# Esquematico.net
KiCad netlist of a schematic drawn in Altium Designer
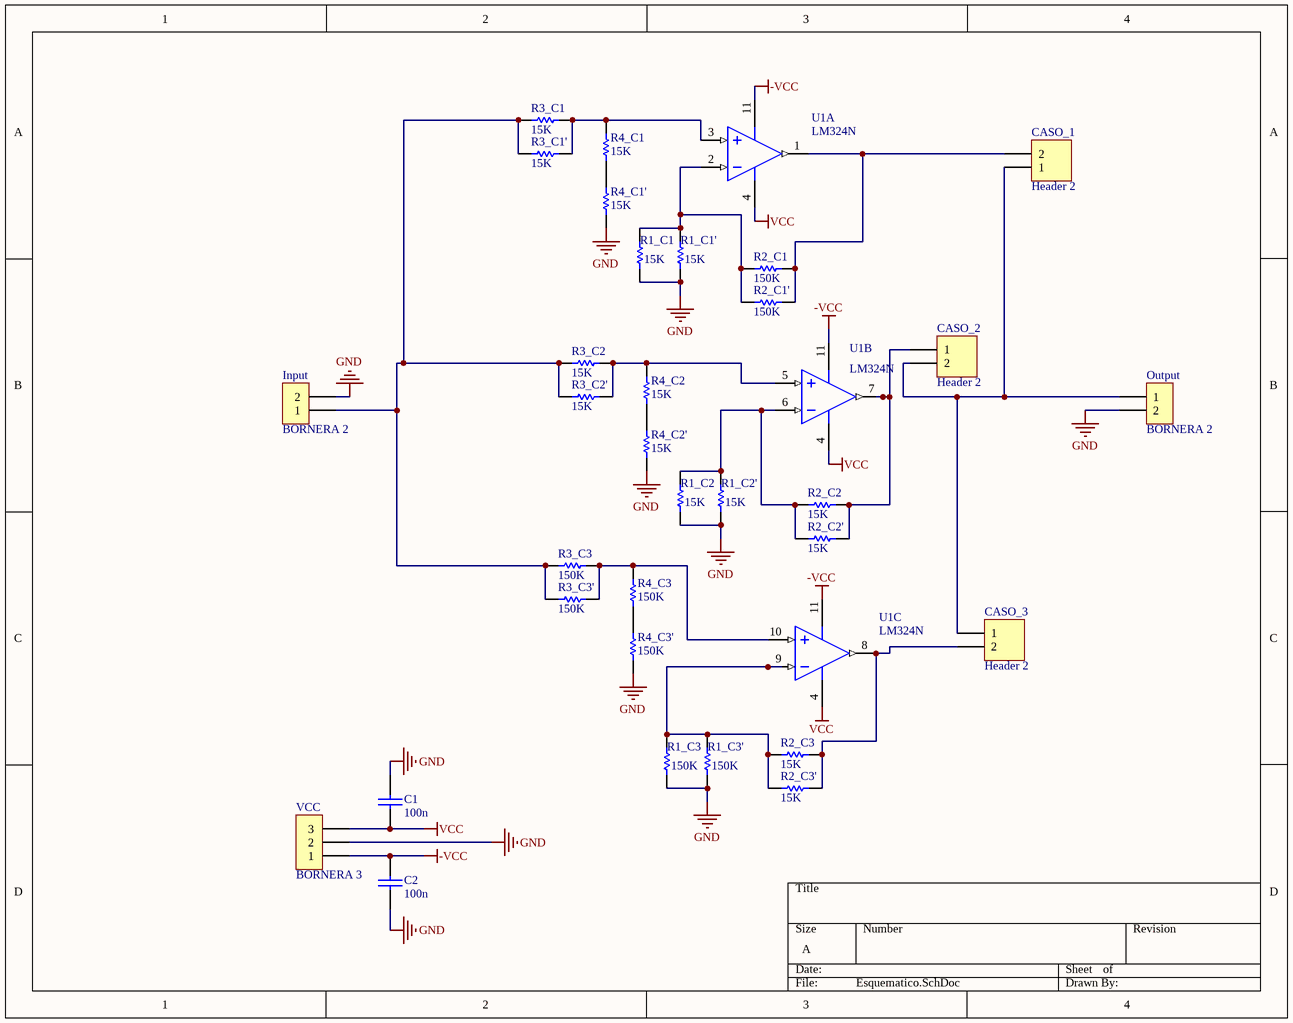
[diagram p0: Esquematico.SchDoc]

(export (version "E")
  (design (tool "Eeschema 10.0.6"))
  (components
    (comp (ref "C1") (value "100n") (footprint "CAP100") (libsource (lib "LIBEBAL") (part "CAP")))
    (comp (ref "C2") (value "100n") (footprint "CAP100") (libsource (lib "LIBEBAL") (part "CAP")))
    (comp (ref "CASO_1")
      (value "Header 2")
      (footprint "HDR1X2")
      (description "Header, 2-Pin")
      (fields (field (name "PUBLISHER") "Altium Limited"))
      (libsource (lib "") (part "Header 2_1"))
    )
    (comp (ref "CASO_2")
      (value "Header 2")
      (footprint "HDR1X2")
      (description "Header, 2-Pin")
      (fields (field (name "PUBLISHER") "Altium Limited"))
      (libsource (lib "Miscellaneous Connectors") (part "Header 2"))
    )
    (comp (ref "CASO_3")
      (value "Header 2")
      (footprint "HDR1X2")
      (description "Header, 2-Pin")
      (fields (field (name "PUBLISHER") "Altium Limited"))
      (libsource (lib "Miscellaneous Connectors") (part "Header 2"))
    )
    (comp (ref "Input") (value "BORNERA 2") (footprint "BORNERA2") (libsource (lib "") (part "BORNERA 2_1")))
    (comp (ref "Output")
      (value "BORNERA 2")
      (footprint "BORNERA2")
      (libsource (lib "LIB PIO IX") (part "BORNERA 2"))
    )
    (comp (ref "R1_C1") (value "15K") (footprint "RES400") (libsource (lib "LIBEBAL") (part "RES")))
    (comp (ref "R1_C1'") (value "15K") (footprint "RES400") (libsource (lib "LIBEBAL") (part "RES")))
    (comp (ref "R1_C2") (value "15K") (footprint "RES400") (libsource (lib "LIBEBAL") (part "RES")))
    (comp (ref "R1_C2'") (value "15K") (footprint "RES400") (libsource (lib "LIBEBAL") (part "RES")))
    (comp (ref "R1_C3") (value "150K") (footprint "RES400") (libsource (lib "LIBEBAL") (part "RES")))
    (comp (ref "R1_C3'") (value "150K") (footprint "RES400") (libsource (lib "LIBEBAL") (part "RES")))
    (comp (ref "R2_C1") (value "150K") (footprint "RES400") (libsource (lib "LIBEBAL") (part "RES")))
    (comp (ref "R2_C1'") (value "150K") (footprint "RES400") (libsource (lib "LIBEBAL") (part "RES")))
    (comp (ref "R2_C2") (value "15K") (footprint "RES400") (libsource (lib "LIBEBAL") (part "RES")))
    (comp (ref "R2_C2'") (value "15K") (footprint "RES400") (libsource (lib "LIBEBAL") (part "RES")))
    (comp (ref "R2_C3") (value "15K") (footprint "RES400") (libsource (lib "LIBEBAL") (part "RES")))
    (comp (ref "R2_C3'") (value "15K") (footprint "RES400") (libsource (lib "LIBEBAL") (part "RES")))
    (comp (ref "R3_C1") (value "15K") (footprint "RES400") (libsource (lib "LIBEBAL") (part "RES")))
    (comp (ref "R3_C1'") (value "15K") (footprint "RES400") (libsource (lib "LIBEBAL") (part "RES")))
    (comp (ref "R3_C2") (value "15K") (footprint "RES400") (libsource (lib "LIBEBAL") (part "RES")))
    (comp (ref "R3_C2'") (value "15K") (footprint "RES400") (libsource (lib "LIBEBAL") (part "RES")))
    (comp (ref "R3_C3") (value "150K") (footprint "RES400") (libsource (lib "LIBEBAL") (part "RES")))
    (comp (ref "R3_C3'") (value "150K") (footprint "RES400") (libsource (lib "LIBEBAL") (part "RES")))
    (comp (ref "R4_C1") (value "15K") (footprint "RES400") (libsource (lib "LIBEBAL") (part "RES")))
    (comp (ref "R4_C1'") (value "15K") (footprint "RES400") (libsource (lib "LIBEBAL") (part "RES")))
    (comp (ref "R4_C2") (value "15K") (footprint "RES400") (libsource (lib "LIBEBAL") (part "RES")))
    (comp (ref "R4_C2'") (value "15K") (footprint "RES400") (libsource (lib "LIBEBAL") (part "RES")))
    (comp (ref "R4_C3") (value "150K") (footprint "RES400") (libsource (lib "LIBEBAL") (part "RES")))
    (comp (ref "R4_C3'") (value "150K") (footprint "RES400") (libsource (lib "LIBEBAL") (part "RES")))
    (comp (ref "U1")
      (value "LM324N")
      (footprint "N14A")
      (description "Low Power Quad Operational Amplifier, 14-pin MDIP")
      (fields
        (field (name "MANUFACTURER") "National Semiconductor")
        (field (name "PUBLISHER") "Altium Limited")
      )
      (libsource (lib "NSC Amplifier") (part "LM324N"))
    )
    (comp (ref "VCC")
      (value "BORNERA 3")
      (footprint "BORNERA3")
      (libsource (lib "LIB PIO IX") (part "BORNERA 3"))
    )
  )
  (nets
    (net (code "1") (name "-VCC") (class "Default")
      (node (ref "C2") (pin "1") (pinfunction "1_1") (pintype "passive"))
      (node (ref "U1") (pin "11") (pinfunction "GND_11") (pintype "power_in"))
      (node (ref "VCC") (pin "1") (pinfunction "1_1") (pintype "passive"))
    )
    (net (code "2") (name "GND") (class "Default")
      (node (ref "C1") (pin "1") (pinfunction "1_1") (pintype "passive"))
      (node (ref "C2") (pin "2") (pinfunction "2_2") (pintype "passive"))
      (node (ref "Input") (pin "2") (pinfunction "2_2") (pintype "passive"))
      (node (ref "Output") (pin "2") (pinfunction "2_2") (pintype "passive"))
      (node (ref "R1_C1") (pin "1") (pinfunction "1_1") (pintype "passive"))
      (node (ref "R1_C1'") (pin "1") (pinfunction "1_1") (pintype "passive"))
      (node (ref "R1_C2") (pin "1") (pinfunction "1_1") (pintype "passive"))
      (node (ref "R1_C2'") (pin "1") (pinfunction "1_1") (pintype "passive"))
      (node (ref "R1_C3") (pin "1") (pinfunction "1_1") (pintype "passive"))
      (node (ref "R1_C3'") (pin "1") (pinfunction "1_1") (pintype "passive"))
      (node (ref "R4_C1'") (pin "1") (pinfunction "1_1") (pintype "passive"))
      (node (ref "R4_C2'") (pin "1") (pinfunction "1_1") (pintype "passive"))
      (node (ref "R4_C3'") (pin "1") (pinfunction "1_1") (pintype "passive"))
      (node (ref "VCC") (pin "2") (pinfunction "2_2") (pintype "passive"))
    )
    (net (code "3") (name "Net-(CASO_1-Pad1)") (class "Default")
      (node (ref "CASO_1") (pin "1") (pinfunction "1_1") (pintype "passive"))
      (node (ref "CASO_2") (pin "2") (pinfunction "2_2") (pintype "passive"))
      (node (ref "CASO_3") (pin "1") (pinfunction "1_1") (pintype "passive"))
      (node (ref "Output") (pin "1") (pinfunction "1_1") (pintype "passive"))
    )
    (net (code "4") (name "Net-(Input-Pad1)") (class "Default")
      (node (ref "Input") (pin "1") (pinfunction "1_1") (pintype "passive"))
      (node (ref "R3_C1") (pin "1") (pinfunction "1_1") (pintype "passive"))
      (node (ref "R3_C1'") (pin "1") (pinfunction "1_1") (pintype "passive"))
      (node (ref "R3_C2") (pin "1") (pinfunction "1_1") (pintype "passive"))
      (node (ref "R3_C2'") (pin "1") (pinfunction "1_1") (pintype "passive"))
      (node (ref "R3_C3") (pin "1") (pinfunction "1_1") (pintype "passive"))
      (node (ref "R3_C3'") (pin "1") (pinfunction "1_1") (pintype "passive"))
    )
    (net (code "5") (name "Net-(R4_C1'-Pad2)") (class "Default")
      (node (ref "R4_C1") (pin "1") (pinfunction "1_1") (pintype "passive"))
      (node (ref "R4_C1'") (pin "2") (pinfunction "2_2") (pintype "passive"))
    )
    (net (code "6") (name "Net-(R4_C2'-Pad2)") (class "Default")
      (node (ref "R4_C2") (pin "1") (pinfunction "1_1") (pintype "passive"))
      (node (ref "R4_C2'") (pin "2") (pinfunction "2_2") (pintype "passive"))
    )
    (net (code "7") (name "Net-(R4_C3'-Pad2)") (class "Default")
      (node (ref "R4_C3") (pin "1") (pinfunction "1_1") (pintype "passive"))
      (node (ref "R4_C3'") (pin "2") (pinfunction "2_2") (pintype "passive"))
    )
    (net (code "8") (name "Net-(U1A-IN1+)") (class "Default")
      (node (ref "R3_C1") (pin "2") (pinfunction "2_2") (pintype "passive"))
      (node (ref "R3_C1'") (pin "2") (pinfunction "2_2") (pintype "passive"))
      (node (ref "R4_C1") (pin "2") (pinfunction "2_2") (pintype "passive"))
      (node (ref "U1") (pin "3") (pinfunction "IN1+_3") (pintype "input"))
    )
    (net (code "9") (name "Net-(U1A-IN1-)") (class "Default")
      (node (ref "R1_C1") (pin "2") (pinfunction "2_2") (pintype "passive"))
      (node (ref "R1_C1'") (pin "2") (pinfunction "2_2") (pintype "passive"))
      (node (ref "R2_C1") (pin "2") (pinfunction "2_2") (pintype "passive"))
      (node (ref "R2_C1'") (pin "2") (pinfunction "2_2") (pintype "passive"))
      (node (ref "U1") (pin "2") (pinfunction "IN1-_2") (pintype "input"))
    )
    (net (code "10") (name "Net-(U1A-OUT1)") (class "Default")
      (node (ref "CASO_1") (pin "2") (pinfunction "2_2") (pintype "passive"))
      (node (ref "R2_C1") (pin "1") (pinfunction "1_1") (pintype "passive"))
      (node (ref "R2_C1'") (pin "1") (pinfunction "1_1") (pintype "passive"))
      (node (ref "U1") (pin "1") (pinfunction "OUT1_1") (pintype "output"))
    )
    (net (code "11") (name "Net-(U1B-IN2+)") (class "Default")
      (node (ref "R3_C2") (pin "2") (pinfunction "2_2") (pintype "passive"))
      (node (ref "R3_C2'") (pin "2") (pinfunction "2_2") (pintype "passive"))
      (node (ref "R4_C2") (pin "2") (pinfunction "2_2") (pintype "passive"))
      (node (ref "U1") (pin "5") (pinfunction "IN2+_5") (pintype "input"))
    )
    (net (code "12") (name "Net-(U1B-IN2-)") (class "Default")
      (node (ref "R1_C2") (pin "2") (pinfunction "2_2") (pintype "passive"))
      (node (ref "R1_C2'") (pin "2") (pinfunction "2_2") (pintype "passive"))
      (node (ref "R2_C2") (pin "2") (pinfunction "2_2") (pintype "passive"))
      (node (ref "R2_C2'") (pin "2") (pinfunction "2_2") (pintype "passive"))
      (node (ref "U1") (pin "6") (pinfunction "IN2-_6") (pintype "input"))
    )
    (net (code "13") (name "Net-(U1B-OUT2)") (class "Default")
      (node (ref "CASO_2") (pin "1") (pinfunction "1_1") (pintype "passive"))
      (node (ref "R2_C2") (pin "1") (pinfunction "1_1") (pintype "passive"))
      (node (ref "R2_C2'") (pin "1") (pinfunction "1_1") (pintype "passive"))
      (node (ref "U1") (pin "7") (pinfunction "OUT2_7") (pintype "output"))
    )
    (net (code "14") (name "Net-(U1C-IN3+)") (class "Default")
      (node (ref "R3_C3") (pin "2") (pinfunction "2_2") (pintype "passive"))
      (node (ref "R3_C3'") (pin "2") (pinfunction "2_2") (pintype "passive"))
      (node (ref "R4_C3") (pin "2") (pinfunction "2_2") (pintype "passive"))
      (node (ref "U1") (pin "10") (pinfunction "IN3+_10") (pintype "input"))
    )
    (net (code "15") (name "Net-(U1C-IN3-)") (class "Default")
      (node (ref "R1_C3") (pin "2") (pinfunction "2_2") (pintype "passive"))
      (node (ref "R1_C3'") (pin "2") (pinfunction "2_2") (pintype "passive"))
      (node (ref "R2_C3") (pin "2") (pinfunction "2_2") (pintype "passive"))
      (node (ref "R2_C3'") (pin "2") (pinfunction "2_2") (pintype "passive"))
      (node (ref "U1") (pin "9") (pinfunction "IN3-_9") (pintype "input"))
    )
    (net (code "16") (name "Net-(U1C-OUT3)") (class "Default")
      (node (ref "CASO_3") (pin "2") (pinfunction "2_2") (pintype "passive"))
      (node (ref "R2_C3") (pin "1") (pinfunction "1_1") (pintype "passive"))
      (node (ref "R2_C3'") (pin "1") (pinfunction "1_1") (pintype "passive"))
      (node (ref "U1") (pin "8") (pinfunction "OUT3_8") (pintype "output"))
    )
    (net (code "17") (name "VCC") (class "Default")
      (node (ref "C1") (pin "2") (pinfunction "2_2") (pintype "passive"))
      (node (ref "U1") (pin "4") (pinfunction "V+_4") (pintype "power_in"))
      (node (ref "VCC") (pin "3") (pinfunction "3_3") (pintype "passive"))
    )
  )
)
